# MCU025B_XDS110_MCU.net
KiCad netlist of a schematic drawn in Altium Designer
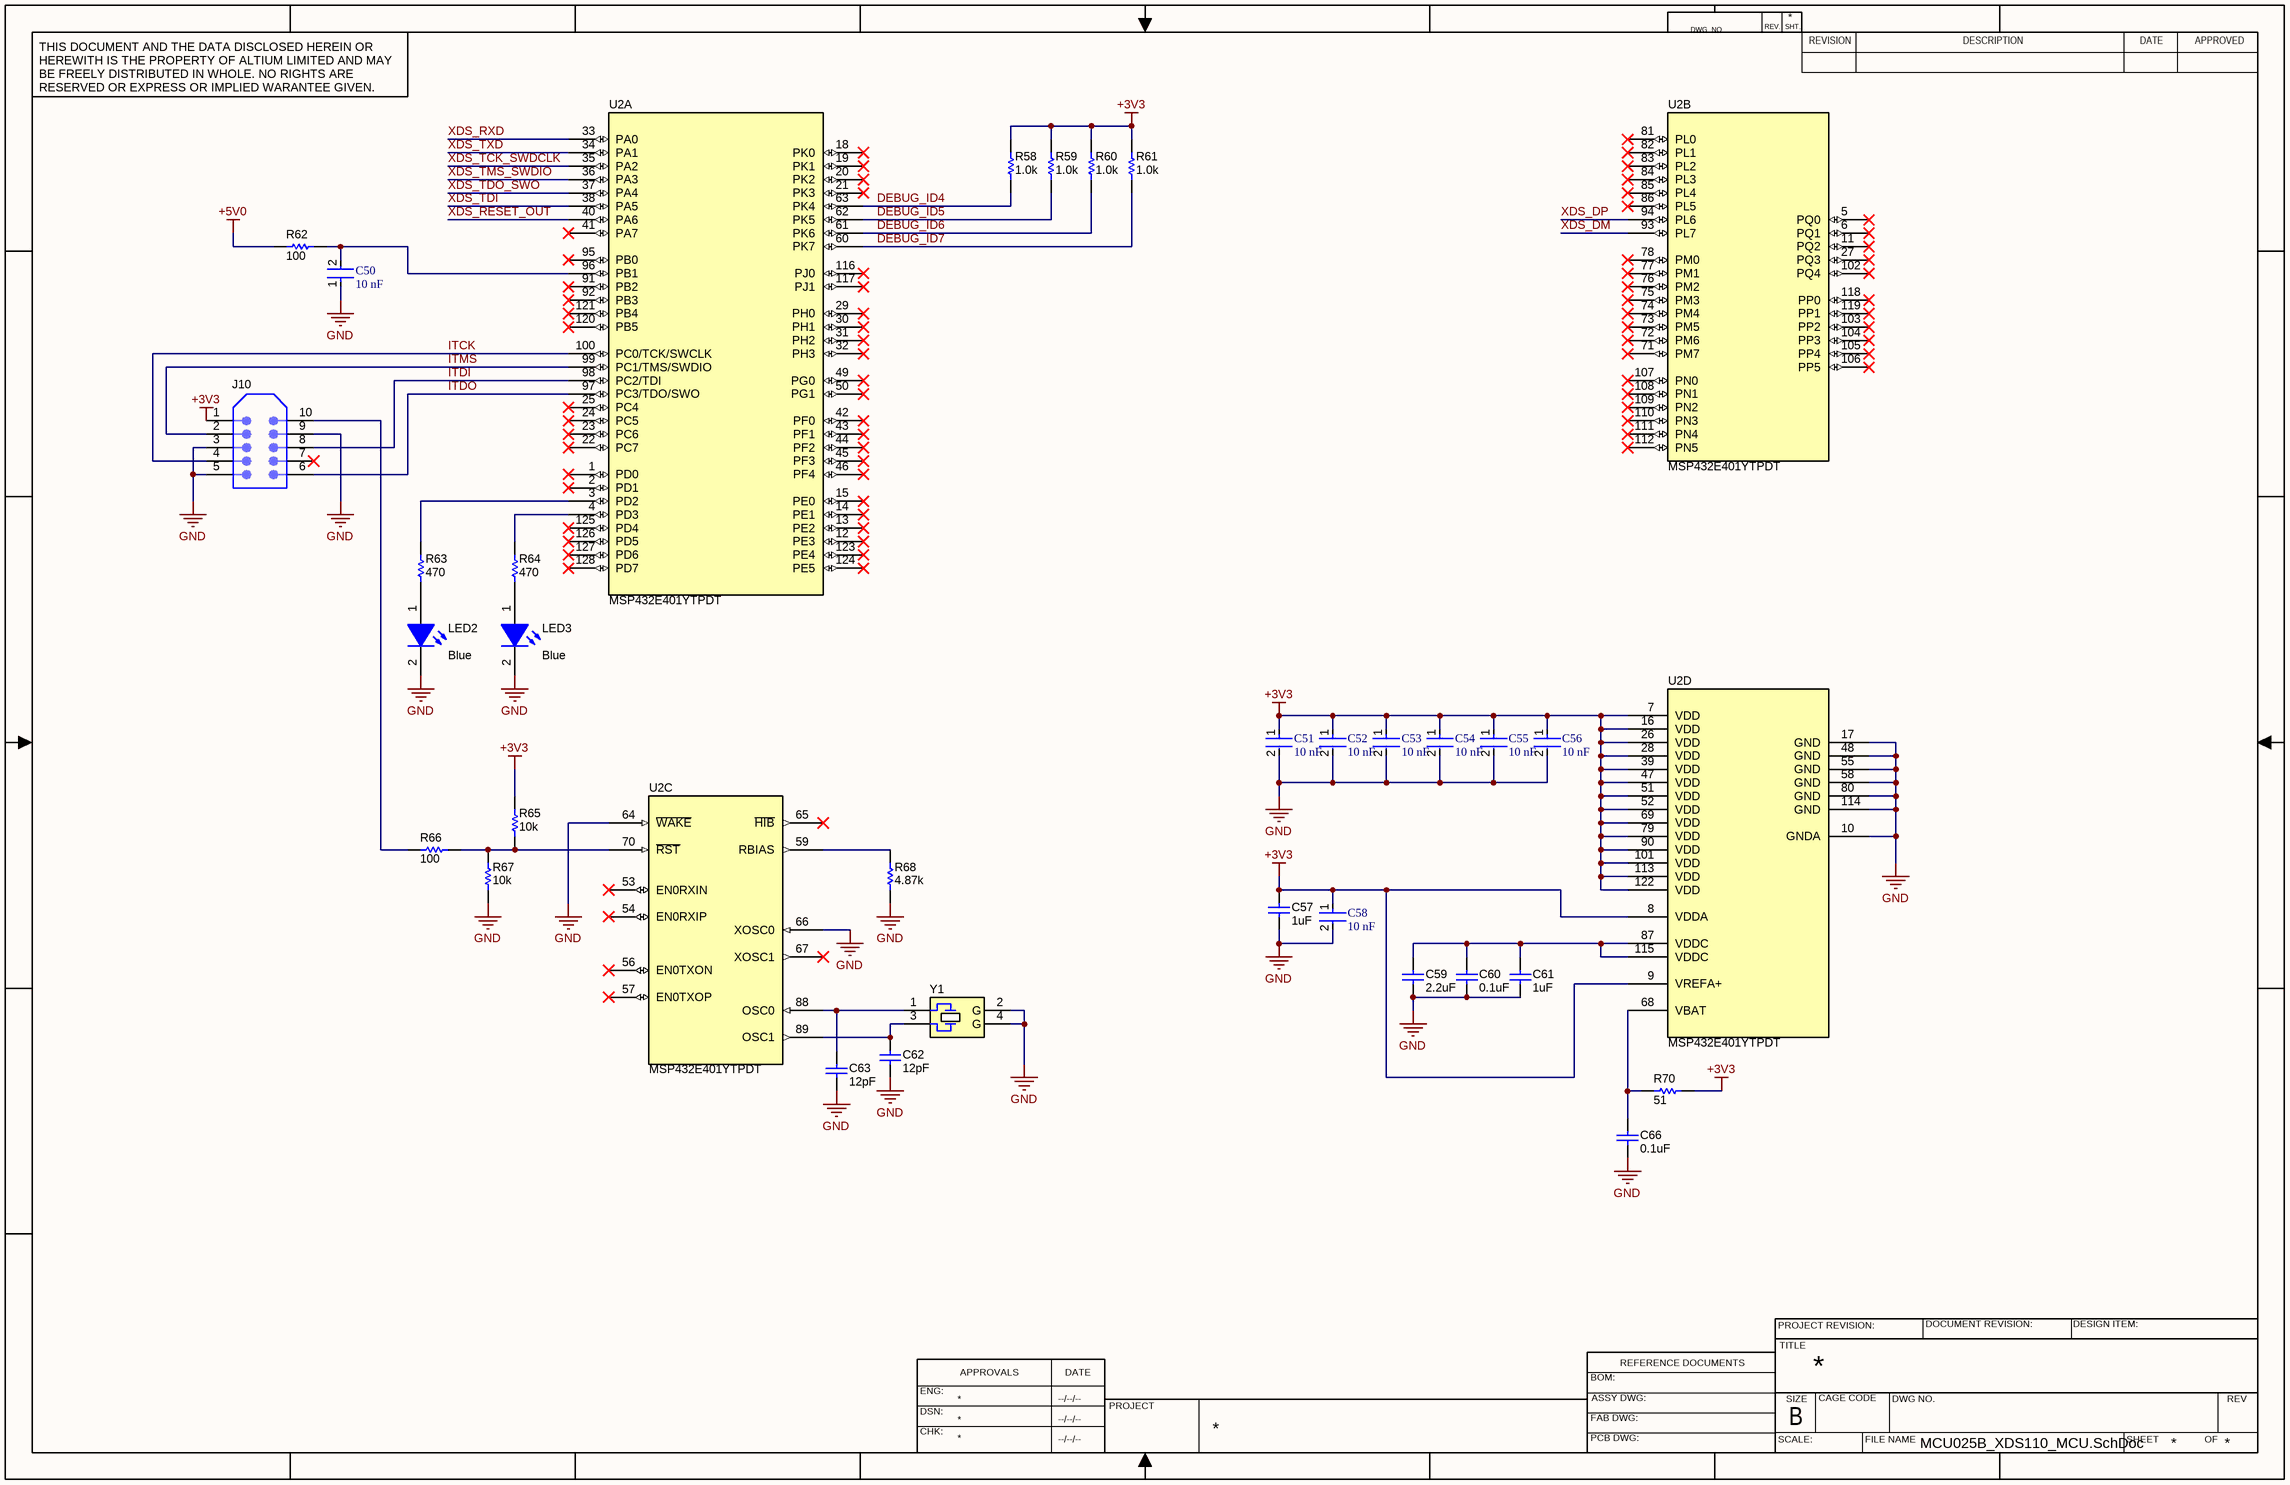
[diagram p0: MCU025B_XDS110_MCU.SchDoc]

(export (version "E")
  (design (tool "Eeschema 10.0.6"))
  (components
    (comp (ref "C50")
      (value "CC0603KRX7R6BB103")
      (footprint "FP-CC0603-DA-MFG")
      (description "CAP CER 10000PF 10V X7R 0603")
      (fields
        (field (name "MANUFACTURER") "YAGEO")
        (field (name "VOLTAGE") "10 V")
        (field (name "CAPACITANCE") "10 nF")
      )
      (libsource (lib "Altium Content Vault") (part "11868f565c42a9108669ba33697ecf6"))
    )
    (comp (ref "C51")
      (value "CC0603KRX7R6BB103")
      (footprint "FP-CC0603-DA-MFG")
      (description "CAP CER 10000PF 10V X7R 0603")
      (fields
        (field (name "MANUFACTURER") "YAGEO")
        (field (name "VOLTAGE") "10 V")
        (field (name "CAPACITANCE") "10 nF")
      )
      (libsource (lib "Altium Content Vault") (part "11868f565c42a9108669ba33697ecf6"))
    )
    (comp (ref "C52")
      (value "CC0603KRX7R6BB103")
      (footprint "FP-CC0603-DA-MFG")
      (description "CAP CER 10000PF 10V X7R 0603")
      (fields
        (field (name "MANUFACTURER") "YAGEO")
        (field (name "VOLTAGE") "10 V")
        (field (name "CAPACITANCE") "10 nF")
      )
      (libsource (lib "Altium Content Vault") (part "11868f565c42a9108669ba33697ecf6"))
    )
    (comp (ref "C53")
      (value "CC0603KRX7R6BB103")
      (footprint "FP-CC0603-DA-MFG")
      (description "CAP CER 10000PF 10V X7R 0603")
      (fields
        (field (name "MANUFACTURER") "YAGEO")
        (field (name "VOLTAGE") "10 V")
        (field (name "CAPACITANCE") "10 nF")
      )
      (libsource (lib "Altium Content Vault") (part "11868f565c42a9108669ba33697ecf6"))
    )
    (comp (ref "C54")
      (value "CC0603KRX7R6BB103")
      (footprint "FP-CC0603-DA-MFG")
      (description "CAP CER 10000PF 10V X7R 0603")
      (fields
        (field (name "MANUFACTURER") "YAGEO")
        (field (name "VOLTAGE") "10 V")
        (field (name "CAPACITANCE") "10 nF")
      )
      (libsource (lib "Altium Content Vault") (part "11868f565c42a9108669ba33697ecf6"))
    )
    (comp (ref "C55")
      (value "CC0603KRX7R6BB103")
      (footprint "FP-CC0603-DA-MFG")
      (description "CAP CER 10000PF 10V X7R 0603")
      (fields
        (field (name "MANUFACTURER") "YAGEO")
        (field (name "VOLTAGE") "10 V")
        (field (name "CAPACITANCE") "10 nF")
      )
      (libsource (lib "Altium Content Vault") (part "11868f565c42a9108669ba33697ecf6"))
    )
    (comp (ref "C56")
      (value "CC0603KRX7R6BB103")
      (footprint "FP-CC0603-DA-MFG")
      (description "CAP CER 10000PF 10V X7R 0603")
      (fields
        (field (name "MANUFACTURER") "YAGEO")
        (field (name "VOLTAGE") "10 V")
        (field (name "CAPACITANCE") "10 nF")
      )
      (libsource (lib "Altium Content Vault") (part "11868f565c42a9108669ba33697ecf6"))
    )
    (comp (ref "C57")
      (value "GRM155R61A105KE15D")
      (footprint "0402")
      (description "CAP, CERM, 1 uF, 10 V, +/- 10%, X5R, 0402")
      (fields
        (field (name "VALUEDISPLAYED") "1uF")
        (field (name "MANUFACTURER") "MuRata")
        (field (name "PUBLISHER") "Texas Instruments")
      )
      (libsource (lib "Altium Vault - TI") (part "Capacitor"))
    )
    (comp (ref "C58")
      (value "CC0603KRX7R6BB103")
      (footprint "FP-CC0603-DA-MFG")
      (description "CAP CER 10000PF 10V X7R 0603")
      (fields
        (field (name "MANUFACTURER") "YAGEO")
        (field (name "VOLTAGE") "10 V")
        (field (name "CAPACITANCE") "10 nF")
      )
      (libsource (lib "Altium Content Vault") (part "11868f565c42a9108669ba33697ecf6"))
    )
    (comp (ref "C59")
      (value "GRM155R60J225KE95D")
      (footprint "0402")
      (description "CAP, CERM, 2.2 uF, 6.3 V, +/- 10%, X5R, 0402")
      (fields
        (field (name "VALUEDISPLAYED") "2.2uF")
        (field (name "MANUFACTURER") "MuRata")
        (field (name "PUBLISHER") "Texas Instruments")
      )
      (libsource (lib "Altium Vault - TI") (part "Capacitor"))
    )
    (comp (ref "C60")
      (value "GRM155R70J104KA01D")
      (footprint "0402")
      (description "CAP, CERM, 0.1 uF, 6.3 V, +/- 10%, X7R, 0402")
      (fields
        (field (name "VALUEDISPLAYED") "0.1uF")
        (field (name "MANUFACTURER") "MuRata")
        (field (name "PUBLISHER") "Texas Instruments")
      )
      (libsource (lib "Altium Vault - TI") (part "Capacitor"))
    )
    (comp (ref "C61")
      (value "GRM155R61A105KE15D")
      (footprint "0402")
      (description "CAP, CERM, 1 uF, 10 V, +/- 10%, X5R, 0402")
      (fields
        (field (name "VALUEDISPLAYED") "1uF")
        (field (name "MANUFACTURER") "MuRata")
        (field (name "PUBLISHER") "Texas Instruments")
      )
      (libsource (lib "Altium Vault - TI") (part "Capacitor"))
    )
    (comp (ref "C62")
      (value "GRM1555C1H120JA01D")
      (footprint "0402")
      (description "CAP, CERM, 12 pF, 50 V, +/- 5%, C0G/NP0, 0402")
      (fields
        (field (name "VALUEDISPLAYED") "12pF")
        (field (name "MANUFACTURER") "MuRata")
        (field (name "PUBLISHER") "Texas Instruments")
      )
      (libsource (lib "Altium Vault - TI") (part "Capacitor"))
    )
    (comp (ref "C63")
      (value "GRM1555C1H120JA01D")
      (footprint "0402")
      (description "CAP, CERM, 12 pF, 50 V, +/- 5%, C0G/NP0, 0402")
      (fields
        (field (name "VALUEDISPLAYED") "12pF")
        (field (name "MANUFACTURER") "MuRata")
        (field (name "PUBLISHER") "Texas Instruments")
      )
      (libsource (lib "Altium Vault - TI") (part "Capacitor"))
    )
    (comp (ref "C66")
      (value "GRM155R70J104KA01D")
      (footprint "0402")
      (description "CAP, CERM, 0.1 uF, 6.3 V, +/- 10%, X7R, 0402")
      (fields
        (field (name "VALUEDISPLAYED") "0.1uF")
        (field (name "MANUFACTURER") "MuRata")
        (field (name "PUBLISHER") "Texas Instruments")
      )
      (libsource (lib "Altium Vault - TI") (part "Capacitor"))
    )
    (comp (ref "J10")
      (value "TC2050-IDC-NL-FP")
      (footprint "Tag_TC2050-NL")
      (description "Footprint for Tag-Connect TC2050 No-Legs cables")
      (fields (field (name "MANUFACTURER") "Tag-Connect") (field (name "PUBLISHER") "Texas Instruments"))
      (libsource (lib "Altium Vault - TI") (part "CMP-0075101-1"))
    )
    (comp (ref "LED2")
      (value "Blue")
      (footprint "LTST-C170TBKT_Blue")
      (description "LED, Blue, SMD")
      (fields
        (field (name "PARTNUMBER") "LTST-C170TBKT")
        (field (name "MANUFACTURER") "Lite-On")
        (field (name "PUBLISHER") "Texas Instruments")
      )
      (libsource (lib "Altium Vault - TI") (part "CMP-0002889-1"))
    )
    (comp (ref "LED3")
      (value "Blue")
      (footprint "LTST-C170TBKT_Blue")
      (description "LED, Blue, SMD")
      (fields
        (field (name "PARTNUMBER") "LTST-C170TBKT")
        (field (name "MANUFACTURER") "Lite-On")
        (field (name "PUBLISHER") "Texas Instruments")
      )
      (libsource (lib "Altium Vault - TI") (part "CMP-0002889-1"))
    )
    (comp (ref "R58")
      (value "CRCW04021K00JNED")
      (footprint "0402")
      (description "RES, 1.0 k, 5%, 0.063 W, AEC-Q200 Grade 0, 0402")
      (fields (field (name "MANUFACTURER") "Vishay-Dale") (field (name "VALUEDISPLAYED") "1.0k"))
      (libsource (lib "Altium Vault - TI") (part "Resistor"))
    )
    (comp (ref "R59")
      (value "CRCW04021K00JNED")
      (footprint "0402")
      (description "RES, 1.0 k, 5%, 0.063 W, AEC-Q200 Grade 0, 0402")
      (fields (field (name "MANUFACTURER") "Vishay-Dale") (field (name "VALUEDISPLAYED") "1.0k"))
      (libsource (lib "Altium Vault - TI") (part "Resistor"))
    )
    (comp (ref "R60")
      (value "CRCW04021K00JNED")
      (footprint "0402")
      (description "RES, 1.0 k, 5%, 0.063 W, AEC-Q200 Grade 0, 0402")
      (fields (field (name "MANUFACTURER") "Vishay-Dale") (field (name "VALUEDISPLAYED") "1.0k"))
      (libsource (lib "Altium Vault - TI") (part "Resistor"))
    )
    (comp (ref "R61")
      (value "CRCW04021K00JNED")
      (footprint "0402")
      (description "RES, 1.0 k, 5%, 0.063 W, AEC-Q200 Grade 0, 0402")
      (fields (field (name "MANUFACTURER") "Vishay-Dale") (field (name "VALUEDISPLAYED") "1.0k"))
      (libsource (lib "Altium Vault - TI") (part "Resistor"))
    )
    (comp (ref "R62")
      (value "CRCW0402100RJNED")
      (footprint "0402")
      (description "RES, 100, 5%, 0.063 W, AEC-Q200 Grade 0, 0402")
      (fields (field (name "VALUEDISPLAYED") "100") (field (name "MANUFACTURER") "Vishay-Dale"))
      (libsource (lib "Altium Vault - TI") (part "Resistor"))
    )
    (comp (ref "R63")
      (value "ERJ-2RKF4700X")
      (footprint "0402")
      (description "RES, 470, 1%, 0.1 W, AEC-Q200 Grade 0, 0402")
      (fields
        (field (name "VALUEDISPLAYED") "470")
        (field (name "MANUFACTURER") "Panasonic")
        (field (name "PUBLISHER") "Texas Instruments")
      )
      (libsource (lib "Altium Vault - TI") (part "Resistor"))
    )
    (comp (ref "R64")
      (value "ERJ-2RKF4700X")
      (footprint "0402")
      (description "RES, 470, 1%, 0.1 W, AEC-Q200 Grade 0, 0402")
      (fields
        (field (name "VALUEDISPLAYED") "470")
        (field (name "MANUFACTURER") "Panasonic")
        (field (name "PUBLISHER") "Texas Instruments")
      )
      (libsource (lib "Altium Vault - TI") (part "Resistor"))
    )
    (comp (ref "R65")
      (value "CRCW040210K0JNED")
      (footprint "0402")
      (description "RES, 10 k, 5%, 0.063 W, AEC-Q200 Grade 0, 0402")
      (fields (field (name "VALUEDISPLAYED") "10k") (field (name "MANUFACTURER") "Vishay-Dale"))
      (libsource (lib "Altium Vault - TI") (part "Resistor"))
    )
    (comp (ref "R66")
      (value "CRCW0402100RJNED")
      (footprint "0402")
      (description "RES, 100, 5%, 0.063 W, AEC-Q200 Grade 0, 0402")
      (fields (field (name "VALUEDISPLAYED") "100") (field (name "MANUFACTURER") "Vishay-Dale"))
      (libsource (lib "Altium Vault - TI") (part "Resistor"))
    )
    (comp (ref "R67")
      (value "CRCW040210K0JNED")
      (footprint "0402")
      (description "RES, 10 k, 5%, 0.063 W, AEC-Q200 Grade 0, 0402")
      (fields (field (name "VALUEDISPLAYED") "10k") (field (name "MANUFACTURER") "Vishay-Dale"))
      (libsource (lib "Altium Vault - TI") (part "Resistor"))
    )
    (comp (ref "R68")
      (value "CRCW04024K87FKED")
      (footprint "0402")
      (description "RES, 4.87 k, 1%, 0.063 W, AEC-Q200 Grade 0, 0402")
      (fields (field (name "VALUEDISPLAYED") "4.87k") (field (name "MANUFACTURER") "Vishay-Dale"))
      (libsource (lib "Altium Vault - TI") (part "Resistor"))
    )
    (comp (ref "R70")
      (value "CRCW040251R0JNED")
      (footprint "0402")
      (description "RES, 51, 5%, 0.063 W, AEC-Q200 Grade 0, 0402")
      (fields (field (name "VALUEDISPLAYED") "51") (field (name "MANUFACTURER") "Vishay-Dale"))
      (libsource (lib "Altium Vault - TI") (part "Resistor"))
    )
    (comp (ref "U2")
      (value "MSP432E401YTPDT")
      (footprint "PDT0128A")
      (description "MSP432E401YTPDT, PDT0128A (TQFP-128)")
      (fields
        (field (name "ALTERNATE PARTNUMBER") "MSP432E401YTPDTR")
        (field (name "MANUFACTURER") "Texas Instruments")
        (field (name "PARTNUMBER") "MSP432E401YTPDT")
      )
      (libsource (lib "Altium Vault - TI") (part "MSP432E401YTPDT"))
    )
    (comp (ref "Y1")
      (value "NX3225GA-16.000M-STD-CRG-1")
      (footprint "NDK_NX3225GA")
      (description "Crystal, 16 MHz, 8pF, SMD")
      (fields (field (name "MANUFACTURER") "NDK"))
      (libsource (lib "Altium Vault - TI") (part "XTAL_4P_13_G24"))
    )
  )
  (nets
    (net (code "1") (name "+3V3") (class "Default")
      (node (ref "C51") (pin "1") (pinfunction "1_1") (pintype "passive"))
      (node (ref "C52") (pin "1") (pinfunction "1_1") (pintype "passive"))
      (node (ref "C53") (pin "1") (pinfunction "1_1") (pintype "passive"))
      (node (ref "C54") (pin "1") (pinfunction "1_1") (pintype "passive"))
      (node (ref "C55") (pin "1") (pinfunction "1_1") (pintype "passive"))
      (node (ref "C56") (pin "1") (pinfunction "1_1") (pintype "passive"))
      (node (ref "C57") (pin "1") (pinfunction "1_1") (pintype "passive"))
      (node (ref "C58") (pin "1") (pinfunction "1_1") (pintype "passive"))
      (node (ref "J10") (pin "1") (pinfunction "1_1") (pintype "passive"))
      (node (ref "R58") (pin "2") (pinfunction "2_2") (pintype "passive"))
      (node (ref "R59") (pin "2") (pinfunction "2_2") (pintype "passive"))
      (node (ref "R60") (pin "2") (pinfunction "2_2") (pintype "passive"))
      (node (ref "R61") (pin "2") (pinfunction "2_2") (pintype "passive"))
      (node (ref "R65") (pin "2") (pinfunction "2_2") (pintype "passive"))
      (node (ref "R70") (pin "2") (pinfunction "2_2") (pintype "passive"))
      (node (ref "U2") (pin "101") (pinfunction "VDD_101") (pintype "power_in"))
      (node (ref "U2") (pin "113") (pinfunction "VDD_113") (pintype "power_in"))
      (node (ref "U2") (pin "122") (pinfunction "VDD_122") (pintype "power_in"))
      (node (ref "U2") (pin "16") (pinfunction "VDD_16") (pintype "power_in"))
      (node (ref "U2") (pin "26") (pinfunction "VDD_26") (pintype "power_in"))
      (node (ref "U2") (pin "28") (pinfunction "VDD_28") (pintype "power_in"))
      (node (ref "U2") (pin "39") (pinfunction "VDD_39") (pintype "power_in"))
      (node (ref "U2") (pin "47") (pinfunction "VDD_47") (pintype "power_in"))
      (node (ref "U2") (pin "51") (pinfunction "VDD_51") (pintype "power_in"))
      (node (ref "U2") (pin "52") (pinfunction "VDD_52") (pintype "power_in"))
      (node (ref "U2") (pin "69") (pinfunction "VDD_69") (pintype "power_in"))
      (node (ref "U2") (pin "7") (pinfunction "VDD_7") (pintype "power_in"))
      (node (ref "U2") (pin "79") (pinfunction "VDD_79") (pintype "power_in"))
      (node (ref "U2") (pin "8") (pinfunction "VDDA_8") (pintype "power_in"))
      (node (ref "U2") (pin "9") (pinfunction "VREFA+_9") (pintype "power_in"))
      (node (ref "U2") (pin "90") (pinfunction "VDD_90") (pintype "power_in"))
    )
    (net (code "2") (name "+5V0") (class "Default")
      (node (ref "R62") (pin "1") (pinfunction "1_1") (pintype "passive"))
    )
    (net (code "3") (name "/DEBUG_ID4") (class "Default")
      (node (ref "R58") (pin "1") (pinfunction "1_1") (pintype "passive"))
      (node (ref "U2") (pin "63") (pinfunction "PK4_63") (pintype "bidirectional"))
    )
    (net (code "4") (name "/DEBUG_ID5") (class "Default")
      (node (ref "R59") (pin "1") (pinfunction "1_1") (pintype "passive"))
      (node (ref "U2") (pin "62") (pinfunction "PK5_62") (pintype "bidirectional"))
    )
    (net (code "5") (name "/DEBUG_ID6") (class "Default")
      (node (ref "R60") (pin "1") (pinfunction "1_1") (pintype "passive"))
      (node (ref "U2") (pin "61") (pinfunction "PK6_61") (pintype "bidirectional"))
    )
    (net (code "6") (name "/DEBUG_ID7") (class "Default")
      (node (ref "R61") (pin "1") (pinfunction "1_1") (pintype "passive"))
      (node (ref "U2") (pin "60") (pinfunction "PK7_60") (pintype "bidirectional"))
    )
    (net (code "7") (name "/ITCK") (class "Default")
      (node (ref "J10") (pin "4") (pinfunction "4_4") (pintype "passive"))
      (node (ref "U2") (pin "100") (pinfunction "PC0/TCK/SWCLK_100") (pintype "bidirectional"))
    )
    (net (code "8") (name "/ITDI") (class "Default")
      (node (ref "J10") (pin "8") (pinfunction "8_8") (pintype "passive"))
      (node (ref "U2") (pin "98") (pinfunction "PC2/TDI_98") (pintype "bidirectional"))
    )
    (net (code "9") (name "/ITDO") (class "Default")
      (node (ref "J10") (pin "6") (pinfunction "6_6") (pintype "passive"))
      (node (ref "U2") (pin "97") (pinfunction "PC3/TDO/SWO_97") (pintype "bidirectional"))
    )
    (net (code "10") (name "/ITMS") (class "Default")
      (node (ref "J10") (pin "2") (pinfunction "2_2") (pintype "passive"))
      (node (ref "U2") (pin "99") (pinfunction "PC1/TMS/SWDIO_99") (pintype "bidirectional"))
    )
    (net (code "11") (name "/XDS_DM") (class "Default")
      (node (ref "U2") (pin "93") (pinfunction "PL7_93") (pintype "bidirectional"))
    )
    (net (code "12") (name "/XDS_DP") (class "Default")
      (node (ref "U2") (pin "94") (pinfunction "PL6_94") (pintype "bidirectional"))
    )
    (net (code "13") (name "/XDS_RESET_OUT") (class "Default")
      (node (ref "U2") (pin "40") (pinfunction "PA6_40") (pintype "bidirectional"))
    )
    (net (code "14") (name "/XDS_RXD") (class "Default")
      (node (ref "U2") (pin "33") (pinfunction "PA0_33") (pintype "bidirectional"))
    )
    (net (code "15") (name "/XDS_TCK_SWDCLK") (class "Default")
      (node (ref "U2") (pin "35") (pinfunction "PA2_35") (pintype "bidirectional"))
    )
    (net (code "16") (name "/XDS_TDI") (class "Default")
      (node (ref "U2") (pin "38") (pinfunction "PA5_38") (pintype "bidirectional"))
    )
    (net (code "17") (name "/XDS_TDO_SWO") (class "Default")
      (node (ref "U2") (pin "37") (pinfunction "PA4_37") (pintype "bidirectional"))
    )
    (net (code "18") (name "/XDS_TMS_SWDIO") (class "Default")
      (node (ref "U2") (pin "36") (pinfunction "PA3_36") (pintype "bidirectional"))
    )
    (net (code "19") (name "/XDS_TXD") (class "Default")
      (node (ref "U2") (pin "34") (pinfunction "PA1_34") (pintype "bidirectional"))
    )
    (net (code "20") (name "GND") (class "Default")
      (node (ref "C50") (pin "1") (pinfunction "1_1") (pintype "passive"))
      (node (ref "C51") (pin "2") (pinfunction "2_2") (pintype "passive"))
      (node (ref "C52") (pin "2") (pinfunction "2_2") (pintype "passive"))
      (node (ref "C53") (pin "2") (pinfunction "2_2") (pintype "passive"))
      (node (ref "C54") (pin "2") (pinfunction "2_2") (pintype "passive"))
      (node (ref "C55") (pin "2") (pinfunction "2_2") (pintype "passive"))
      (node (ref "C56") (pin "2") (pinfunction "2_2") (pintype "passive"))
      (node (ref "C57") (pin "2") (pinfunction "2_2") (pintype "passive"))
      (node (ref "C58") (pin "2") (pinfunction "2_2") (pintype "passive"))
      (node (ref "C59") (pin "2") (pinfunction "2_2") (pintype "passive"))
      (node (ref "C60") (pin "2") (pinfunction "2_2") (pintype "passive"))
      (node (ref "C61") (pin "2") (pinfunction "2_2") (pintype "passive"))
      (node (ref "C62") (pin "2") (pinfunction "2_2") (pintype "passive"))
      (node (ref "C63") (pin "2") (pinfunction "2_2") (pintype "passive"))
      (node (ref "C66") (pin "2") (pinfunction "2_2") (pintype "passive"))
      (node (ref "J10") (pin "3") (pinfunction "3_3") (pintype "passive"))
      (node (ref "J10") (pin "5") (pinfunction "5_5") (pintype "passive"))
      (node (ref "J10") (pin "9") (pinfunction "9_9") (pintype "passive"))
      (node (ref "LED2") (pin "2") (pinfunction "K_2") (pintype "passive"))
      (node (ref "LED3") (pin "2") (pinfunction "K_2") (pintype "passive"))
      (node (ref "R67") (pin "1") (pinfunction "1_1") (pintype "passive"))
      (node (ref "R68") (pin "1") (pinfunction "1_1") (pintype "passive"))
      (node (ref "U2") (pin "10") (pinfunction "GNDA_10") (pintype "power_in"))
      (node (ref "U2") (pin "114") (pinfunction "GND_114") (pintype "power_in"))
      (node (ref "U2") (pin "17") (pinfunction "GND_17") (pintype "power_in"))
      (node (ref "U2") (pin "48") (pinfunction "GND_48") (pintype "power_in"))
      (node (ref "U2") (pin "55") (pinfunction "GND_55") (pintype "power_in"))
      (node (ref "U2") (pin "58") (pinfunction "GND_58") (pintype "power_in"))
      (node (ref "U2") (pin "64") (pinfunction "WAKE_64") (pintype "input"))
      (node (ref "U2") (pin "66") (pinfunction "XOSC0_66") (pintype "input"))
      (node (ref "U2") (pin "80") (pinfunction "GND_80") (pintype "power_in"))
      (node (ref "Y1") (pin "2") (pinfunction "GND_2") (pintype "power_in"))
      (node (ref "Y1") (pin "4") (pinfunction "GND_4") (pintype "power_in"))
    )
    (net (code "21") (name "Net-(C59-Pad1)") (class "Default")
      (node (ref "C59") (pin "1") (pinfunction "1_1") (pintype "passive"))
      (node (ref "C60") (pin "1") (pinfunction "1_1") (pintype "passive"))
      (node (ref "C61") (pin "1") (pinfunction "1_1") (pintype "passive"))
      (node (ref "U2") (pin "115") (pinfunction "VDDC_115") (pintype "power_in"))
      (node (ref "U2") (pin "87") (pinfunction "VDDC_87") (pintype "power_in"))
    )
    (net (code "22") (name "Net-(J10-Pad10)") (class "Default")
      (node (ref "J10") (pin "10") (pinfunction "10_10") (pintype "passive"))
      (node (ref "R66") (pin "1") (pinfunction "1_1") (pintype "passive"))
    )
    (net (code "23") (name "Net-(LED2-A)") (class "Default")
      (node (ref "LED2") (pin "1") (pinfunction "A_1") (pintype "passive"))
      (node (ref "R63") (pin "1") (pinfunction "1_1") (pintype "passive"))
    )
    (net (code "24") (name "Net-(LED3-A)") (class "Default")
      (node (ref "LED3") (pin "1") (pinfunction "A_1") (pintype "passive"))
      (node (ref "R64") (pin "1") (pinfunction "1_1") (pintype "passive"))
    )
    (net (code "25") (name "Net-(U2A-PB1)") (class "Default")
      (node (ref "C50") (pin "2") (pinfunction "2_2") (pintype "passive"))
      (node (ref "R62") (pin "2") (pinfunction "2_2") (pintype "passive"))
      (node (ref "U2") (pin "96") (pinfunction "PB1_96") (pintype "bidirectional"))
    )
    (net (code "26") (name "Net-(U2A-PD2)") (class "Default")
      (node (ref "R63") (pin "2") (pinfunction "2_2") (pintype "passive"))
      (node (ref "U2") (pin "3") (pinfunction "PD2_3") (pintype "bidirectional"))
    )
    (net (code "27") (name "Net-(U2A-PD3)") (class "Default")
      (node (ref "R64") (pin "2") (pinfunction "2_2") (pintype "passive"))
      (node (ref "U2") (pin "4") (pinfunction "PD3_4") (pintype "bidirectional"))
    )
    (net (code "28") (name "Net-(U2C-OSC0)") (class "Default")
      (node (ref "C63") (pin "1") (pinfunction "1_1") (pintype "passive"))
      (node (ref "U2") (pin "88") (pinfunction "OSC0_88") (pintype "input"))
      (node (ref "Y1") (pin "1") (pinfunction "1_1") (pintype "passive"))
    )
    (net (code "29") (name "Net-(U2C-OSC1)") (class "Default")
      (node (ref "C62") (pin "1") (pinfunction "1_1") (pintype "passive"))
      (node (ref "U2") (pin "89") (pinfunction "OSC1_89") (pintype "output"))
      (node (ref "Y1") (pin "3") (pinfunction "3_3") (pintype "passive"))
    )
    (net (code "30") (name "Net-(U2C-RBIAS)") (class "Default")
      (node (ref "R68") (pin "2") (pinfunction "2_2") (pintype "passive"))
      (node (ref "U2") (pin "59") (pinfunction "RBIAS_59") (pintype "output"))
    )
    (net (code "31") (name "Net-(U2C-RST)") (class "Default")
      (node (ref "R65") (pin "1") (pinfunction "1_1") (pintype "passive"))
      (node (ref "R66") (pin "2") (pinfunction "2_2") (pintype "passive"))
      (node (ref "R67") (pin "2") (pinfunction "2_2") (pintype "passive"))
      (node (ref "U2") (pin "70") (pinfunction "RST_70") (pintype "input"))
    )
    (net (code "32") (name "Net-(U2D-VBAT)") (class "Default")
      (node (ref "C66") (pin "1") (pinfunction "1_1") (pintype "passive"))
      (node (ref "R70") (pin "1") (pinfunction "1_1") (pintype "passive"))
      (node (ref "U2") (pin "68") (pinfunction "VBAT_68") (pintype "power_in"))
    )
    (net (code "33") (name "unconnected-(J10-Pad7)") (class "Default")
      (node (ref "J10") (pin "7") (pinfunction "7_7") (pintype "passive+no_connect"))
    )
    (net (code "34") (name "unconnected-(U2A-PA7-Pad41)") (class "Default")
      (node (ref "U2") (pin "41") (pinfunction "PA7_41") (pintype "bidirectional+no_connect"))
    )
    (net (code "35") (name "unconnected-(U2A-PB0-Pad95)") (class "Default")
      (node (ref "U2") (pin "95") (pinfunction "PB0_95") (pintype "bidirectional+no_connect"))
    )
    (net (code "36") (name "unconnected-(U2A-PB2-Pad91)") (class "Default")
      (node (ref "U2") (pin "91") (pinfunction "PB2_91") (pintype "bidirectional+no_connect"))
    )
    (net (code "37") (name "unconnected-(U2A-PB3-Pad92)") (class "Default")
      (node (ref "U2") (pin "92") (pinfunction "PB3_92") (pintype "bidirectional+no_connect"))
    )
    (net (code "38") (name "unconnected-(U2A-PB4-Pad121)") (class "Default")
      (node (ref "U2") (pin "121") (pinfunction "PB4_121") (pintype "bidirectional+no_connect"))
    )
    (net (code "39") (name "unconnected-(U2A-PB5-Pad120)") (class "Default")
      (node (ref "U2") (pin "120") (pinfunction "PB5_120") (pintype "bidirectional+no_connect"))
    )
    (net (code "40") (name "unconnected-(U2A-PC4-Pad25)") (class "Default")
      (node (ref "U2") (pin "25") (pinfunction "PC4_25") (pintype "bidirectional+no_connect"))
    )
    (net (code "41") (name "unconnected-(U2A-PC5-Pad24)") (class "Default")
      (node (ref "U2") (pin "24") (pinfunction "PC5_24") (pintype "bidirectional+no_connect"))
    )
    (net (code "42") (name "unconnected-(U2A-PC6-Pad23)") (class "Default")
      (node (ref "U2") (pin "23") (pinfunction "PC6_23") (pintype "bidirectional+no_connect"))
    )
    (net (code "43") (name "unconnected-(U2A-PC7-Pad22)") (class "Default")
      (node (ref "U2") (pin "22") (pinfunction "PC7_22") (pintype "bidirectional+no_connect"))
    )
    (net (code "44") (name "unconnected-(U2A-PD0-Pad1)") (class "Default")
      (node (ref "U2") (pin "1") (pinfunction "PD0_1") (pintype "bidirectional+no_connect"))
    )
    (net (code "45") (name "unconnected-(U2A-PD1-Pad2)") (class "Default")
      (node (ref "U2") (pin "2") (pinfunction "PD1_2") (pintype "bidirectional+no_connect"))
    )
    (net (code "46") (name "unconnected-(U2A-PD4-Pad125)") (class "Default")
      (node (ref "U2") (pin "125") (pinfunction "PD4_125") (pintype "bidirectional+no_connect"))
    )
    (net (code "47") (name "unconnected-(U2A-PD5-Pad126)") (class "Default")
      (node (ref "U2") (pin "126") (pinfunction "PD5_126") (pintype "bidirectional+no_connect"))
    )
    (net (code "48") (name "unconnected-(U2A-PD6-Pad127)") (class "Default")
      (node (ref "U2") (pin "127") (pinfunction "PD6_127") (pintype "bidirectional+no_connect"))
    )
    (net (code "49") (name "unconnected-(U2A-PD7-Pad128)") (class "Default")
      (node (ref "U2") (pin "128") (pinfunction "PD7_128") (pintype "bidirectional+no_connect"))
    )
    (net (code "50") (name "unconnected-(U2A-PE0-Pad15)") (class "Default")
      (node (ref "U2") (pin "15") (pinfunction "PE0_15") (pintype "bidirectional+no_connect"))
    )
    (net (code "51") (name "unconnected-(U2A-PE1-Pad14)") (class "Default")
      (node (ref "U2") (pin "14") (pinfunction "PE1_14") (pintype "bidirectional+no_connect"))
    )
    (net (code "52") (name "unconnected-(U2A-PE2-Pad13)") (class "Default")
      (node (ref "U2") (pin "13") (pinfunction "PE2_13") (pintype "bidirectional+no_connect"))
    )
    (net (code "53") (name "unconnected-(U2A-PE3-Pad12)") (class "Default")
      (node (ref "U2") (pin "12") (pinfunction "PE3_12") (pintype "bidirectional+no_connect"))
    )
    (net (code "54") (name "unconnected-(U2A-PE4-Pad123)") (class "Default")
      (node (ref "U2") (pin "123") (pinfunction "PE4_123") (pintype "bidirectional+no_connect"))
    )
    (net (code "55") (name "unconnected-(U2A-PE5-Pad124)") (class "Default")
      (node (ref "U2") (pin "124") (pinfunction "PE5_124") (pintype "bidirectional+no_connect"))
    )
    (net (code "56") (name "unconnected-(U2A-PF0-Pad42)") (class "Default")
      (node (ref "U2") (pin "42") (pinfunction "PF0_42") (pintype "bidirectional+no_connect"))
    )
    (net (code "57") (name "unconnected-(U2A-PF1-Pad43)") (class "Default")
      (node (ref "U2") (pin "43") (pinfunction "PF1_43") (pintype "bidirectional+no_connect"))
    )
    (net (code "58") (name "unconnected-(U2A-PF2-Pad44)") (class "Default")
      (node (ref "U2") (pin "44") (pinfunction "PF2_44") (pintype "bidirectional+no_connect"))
    )
    (net (code "59") (name "unconnected-(U2A-PF3-Pad45)") (class "Default")
      (node (ref "U2") (pin "45") (pinfunction "PF3_45") (pintype "bidirectional+no_connect"))
    )
    (net (code "60") (name "unconnected-(U2A-PF4-Pad46)") (class "Default")
      (node (ref "U2") (pin "46") (pinfunction "PF4_46") (pintype "bidirectional+no_connect"))
    )
    (net (code "61") (name "unconnected-(U2A-PG0-Pad49)") (class "Default")
      (node (ref "U2") (pin "49") (pinfunction "PG0_49") (pintype "bidirectional+no_connect"))
    )
    (net (code "62") (name "unconnected-(U2A-PG1-Pad50)") (class "Default")
      (node (ref "U2") (pin "50") (pinfunction "PG1_50") (pintype "bidirectional+no_connect"))
    )
    (net (code "63") (name "unconnected-(U2A-PH0-Pad29)") (class "Default")
      (node (ref "U2") (pin "29") (pinfunction "PH0_29") (pintype "bidirectional+no_connect"))
    )
    (net (code "64") (name "unconnected-(U2A-PH1-Pad30)") (class "Default")
      (node (ref "U2") (pin "30") (pinfunction "PH1_30") (pintype "bidirectional+no_connect"))
    )
    (net (code "65") (name "unconnected-(U2A-PH2-Pad31)") (class "Default")
      (node (ref "U2") (pin "31") (pinfunction "PH2_31") (pintype "bidirectional+no_connect"))
    )
    (net (code "66") (name "unconnected-(U2A-PH3-Pad32)") (class "Default")
      (node (ref "U2") (pin "32") (pinfunction "PH3_32") (pintype "bidirectional+no_connect"))
    )
    (net (code "67") (name "unconnected-(U2A-PJ0-Pad116)") (class "Default")
      (node (ref "U2") (pin "116") (pinfunction "PJ0_116") (pintype "bidirectional+no_connect"))
    )
    (net (code "68") (name "unconnected-(U2A-PJ1-Pad117)") (class "Default")
      (node (ref "U2") (pin "117") (pinfunction "PJ1_117") (pintype "bidirectional+no_connect"))
    )
    (net (code "69") (name "unconnected-(U2A-PK0-Pad18)") (class "Default")
      (node (ref "U2") (pin "18") (pinfunction "PK0_18") (pintype "bidirectional+no_connect"))
    )
    (net (code "70") (name "unconnected-(U2A-PK1-Pad19)") (class "Default")
      (node (ref "U2") (pin "19") (pinfunction "PK1_19") (pintype "bidirectional+no_connect"))
    )
    (net (code "71") (name "unconnected-(U2A-PK2-Pad20)") (class "Default")
      (node (ref "U2") (pin "20") (pinfunction "PK2_20") (pintype "bidirectional+no_connect"))
    )
    (net (code "72") (name "unconnected-(U2A-PK3-Pad21)") (class "Default")
      (node (ref "U2") (pin "21") (pinfunction "PK3_21") (pintype "bidirectional+no_connect"))
    )
    (net (code "73") (name "unconnected-(U2B-PL0-Pad81)") (class "Default")
      (node (ref "U2") (pin "81") (pinfunction "PL0_81") (pintype "bidirectional+no_connect"))
    )
    (net (code "74") (name "unconnected-(U2B-PL1-Pad82)") (class "Default")
      (node (ref "U2") (pin "82") (pinfunction "PL1_82") (pintype "bidirectional+no_connect"))
    )
    (net (code "75") (name "unconnected-(U2B-PL2-Pad83)") (class "Default")
      (node (ref "U2") (pin "83") (pinfunction "PL2_83") (pintype "bidirectional+no_connect"))
    )
    (net (code "76") (name "unconnected-(U2B-PL3-Pad84)") (class "Default")
      (node (ref "U2") (pin "84") (pinfunction "PL3_84") (pintype "bidirectional+no_connect"))
    )
    (net (code "77") (name "unconnected-(U2B-PL4-Pad85)") (class "Default")
      (node (ref "U2") (pin "85") (pinfunction "PL4_85") (pintype "bidirectional+no_connect"))
    )
    (net (code "78") (name "unconnected-(U2B-PL5-Pad86)") (class "Default")
      (node (ref "U2") (pin "86") (pinfunction "PL5_86") (pintype "bidirectional+no_connect"))
    )
    (net (code "79") (name "unconnected-(U2B-PM0-Pad78)") (class "Default")
      (node (ref "U2") (pin "78") (pinfunction "PM0_78") (pintype "bidirectional+no_connect"))
    )
    (net (code "80") (name "unconnected-(U2B-PM1-Pad77)") (class "Default")
      (node (ref "U2") (pin "77") (pinfunction "PM1_77") (pintype "bidirectional+no_connect"))
    )
    (net (code "81") (name "unconnected-(U2B-PM2-Pad76)") (class "Default")
      (node (ref "U2") (pin "76") (pinfunction "PM2_76") (pintype "bidirectional+no_connect"))
    )
    (net (code "82") (name "unconnected-(U2B-PM3-Pad75)") (class "Default")
      (node (ref "U2") (pin "75") (pinfunction "PM3_75") (pintype "bidirectional+no_connect"))
    )
    (net (code "83") (name "unconnected-(U2B-PM4-Pad74)") (class "Default")
      (node (ref "U2") (pin "74") (pinfunction "PM4_74") (pintype "bidirectional+no_connect"))
    )
    (net (code "84") (name "unconnected-(U2B-PM5-Pad73)") (class "Default")
      (node (ref "U2") (pin "73") (pinfunction "PM5_73") (pintype "bidirectional+no_connect"))
    )
    (net (code "85") (name "unconnected-(U2B-PM6-Pad72)") (class "Default")
      (node (ref "U2") (pin "72") (pinfunction "PM6_72") (pintype "bidirectional+no_connect"))
    )
    (net (code "86") (name "unconnected-(U2B-PM7-Pad71)") (class "Default")
      (node (ref "U2") (pin "71") (pinfunction "PM7_71") (pintype "bidirectional+no_connect"))
    )
    (net (code "87") (name "unconnected-(U2B-PN0-Pad107)") (class "Default")
      (node (ref "U2") (pin "107") (pinfunction "PN0_107") (pintype "bidirectional+no_connect"))
    )
    (net (code "88") (name "unconnected-(U2B-PN1-Pad108)") (class "Default")
      (node (ref "U2") (pin "108") (pinfunction "PN1_108") (pintype "bidirectional+no_connect"))
    )
    (net (code "89") (name "unconnected-(U2B-PN2-Pad109)") (class "Default")
      (node (ref "U2") (pin "109") (pinfunction "PN2_109") (pintype "bidirectional+no_connect"))
    )
    (net (code "90") (name "unconnected-(U2B-PN3-Pad110)") (class "Default")
      (node (ref "U2") (pin "110") (pinfunction "PN3_110") (pintype "bidirectional+no_connect"))
    )
    (net (code "91") (name "unconnected-(U2B-PN4-Pad111)") (class "Default")
      (node (ref "U2") (pin "111") (pinfunction "PN4_111") (pintype "bidirectional+no_connect"))
    )
    (net (code "92") (name "unconnected-(U2B-PN5-Pad112)") (class "Default")
      (node (ref "U2") (pin "112") (pinfunction "PN5_112") (pintype "bidirectional+no_connect"))
    )
    (net (code "93") (name "unconnected-(U2B-PP0-Pad118)") (class "Default")
      (node (ref "U2") (pin "118") (pinfunction "PP0_118") (pintype "bidirectional+no_connect"))
    )
    (net (code "94") (name "unconnected-(U2B-PP1-Pad119)") (class "Default")
      (node (ref "U2") (pin "119") (pinfunction "PP1_119") (pintype "bidirectional+no_connect"))
    )
    (net (code "95") (name "unconnected-(U2B-PP2-Pad103)") (class "Default")
      (node (ref "U2") (pin "103") (pinfunction "PP2_103") (pintype "bidirectional+no_connect"))
    )
    (net (code "96") (name "unconnected-(U2B-PP3-Pad104)") (class "Default")
      (node (ref "U2") (pin "104") (pinfunction "PP3_104") (pintype "bidirectional+no_connect"))
    )
    (net (code "97") (name "unconnected-(U2B-PP4-Pad105)") (class "Default")
      (node (ref "U2") (pin "105") (pinfunction "PP4_105") (pintype "bidirectional+no_connect"))
    )
    (net (code "98") (name "unconnected-(U2B-PP5-Pad106)") (class "Default")
      (node (ref "U2") (pin "106") (pinfunction "PP5_106") (pintype "bidirectional+no_connect"))
    )
    (net (code "99") (name "unconnected-(U2B-PQ0-Pad5)") (class "Default")
      (node (ref "U2") (pin "5") (pinfunction "PQ0_5") (pintype "bidirectional+no_connect"))
    )
    (net (code "100") (name "unconnected-(U2B-PQ1-Pad6)") (class "Default")
      (node (ref "U2") (pin "6") (pinfunction "PQ1_6") (pintype "bidirectional+no_connect"))
    )
    (net (code "101") (name "unconnected-(U2B-PQ2-Pad11)") (class "Default")
      (node (ref "U2") (pin "11") (pinfunction "PQ2_11") (pintype "bidirectional+no_connect"))
    )
    (net (code "102") (name "unconnected-(U2B-PQ3-Pad27)") (class "Default")
      (node (ref "U2") (pin "27") (pinfunction "PQ3_27") (pintype "bidirectional+no_connect"))
    )
    (net (code "103") (name "unconnected-(U2B-PQ4-Pad102)") (class "Default")
      (node (ref "U2") (pin "102") (pinfunction "PQ4_102") (pintype "bidirectional+no_connect"))
    )
    (net (code "104") (name "unconnected-(U2C-EN0RXIN-Pad53)") (class "Default")
      (node (ref "U2") (pin "53") (pinfunction "EN0RXIN_53") (pintype "bidirectional+no_connect"))
    )
    (net (code "105") (name "unconnected-(U2C-EN0RXIP-Pad54)") (class "Default")
      (node (ref "U2") (pin "54") (pinfunction "EN0RXIP_54") (pintype "bidirectional+no_connect"))
    )
    (net (code "106") (name "unconnected-(U2C-EN0TXON-Pad56)") (class "Default")
      (node (ref "U2") (pin "56") (pinfunction "EN0TXON_56") (pintype "bidirectional+no_connect"))
    )
    (net (code "107") (name "unconnected-(U2C-EN0TXOP-Pad57)") (class "Default")
      (node (ref "U2") (pin "57") (pinfunction "EN0TXOP_57") (pintype "bidirectional+no_connect"))
    )
    (net (code "108") (name "unconnected-(U2C-HIB-Pad65)") (class "Default")
      (node (ref "U2") (pin "65") (pinfunction "HIB_65") (pintype "output+no_connect"))
    )
    (net (code "109") (name "unconnected-(U2C-XOSC1-Pad67)") (class "Default")
      (node (ref "U2") (pin "67") (pinfunction "XOSC1_67") (pintype "output+no_connect"))
    )
  )
)
